# Anand1-PPG-Module.net
KiCad netlist of a schematic drawn in EAGLE
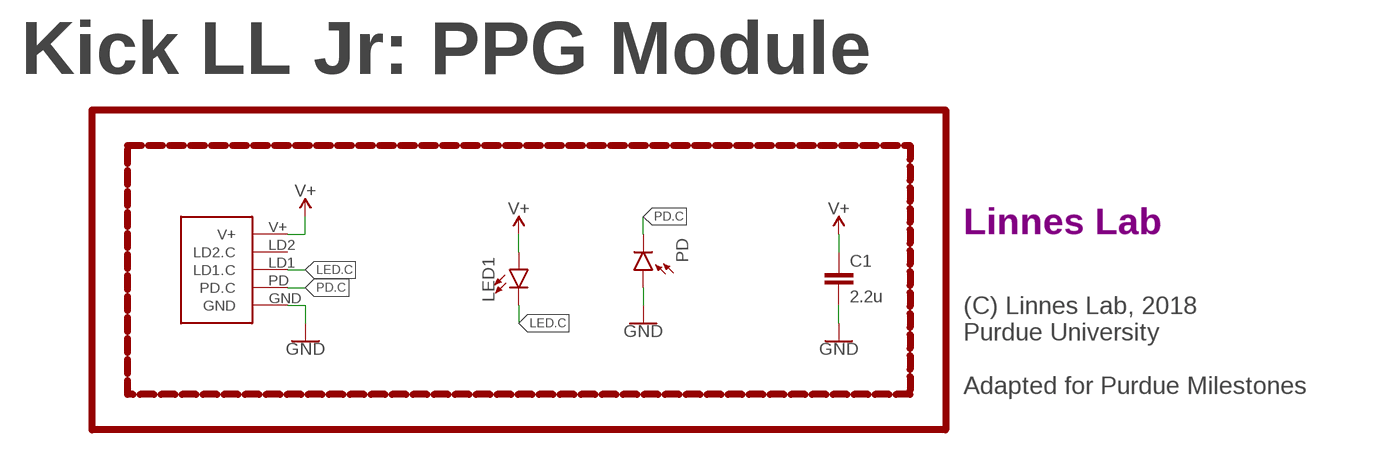
[diagram p0: schematic, sheet 1]

(export (version "E")
  (design (tool "Eeschema 10.0.6"))
  (components
    (comp (ref "C1")
      (value "2.2u")
      (footprint "eagle-import:C0603")
      (libsource (lib "eagle-import") (part "CAPACITOR0603"))
    )
    (comp (ref "J1")
      (value "PPG.MODULE.2")
      (footprint "eagle-import:PPG.MODULE.2")
      (libsource (lib "eagle-import") (part "PPG.MODULE.2"))
    )
    (comp (ref "LED1")
      (value "LED0805")
      (footprint "eagle-import:LED-0805")
      (libsource (lib "eagle-import") (part "LED0805"))
    )
    (comp (ref "PD")
      (value "PHOTODIODE.-SMD.GULLWING")
      (footprint "eagle-import:2-SMD.GULLWING")
      (libsource (lib "eagle-import") (part "PHOTODIODE.-SMD.GULLWING"))
    )
    (comp (ref "U$3")
      (value "LINNES.LAB.LOGO")
      (footprint "eagle-import:LINNES.LAB.LOGO")
      (libsource (lib "eagle-import") (part "LINNES.LAB.LOGO"))
    )
  )
  (nets
    (net (code "1") (name "GND") (class "Default")
      (node (ref "C1") (pin "2") (pinfunction "2_2") (pintype "passive"))
      (node (ref "J1") (pin "GND") (pinfunction "GND_GND") (pintype "bidirectional"))
      (node (ref "PD") (pin "+") (pinfunction "A_+") (pintype "passive"))
    )
    (net (code "2") (name "LED.C") (class "Default")
      (node (ref "J1") (pin "LD1") (pinfunction "LD1.C_LD1") (pintype "bidirectional"))
      (node (ref "LED1") (pin "C") (pinfunction "C_C") (pintype "passive"))
    )
    (net (code "3") (name "PD.C") (class "Default")
      (node (ref "J1") (pin "PD") (pinfunction "PD.C_PD") (pintype "bidirectional"))
      (node (ref "PD") (pin "-") (pinfunction "C_-") (pintype "passive"))
    )
    (net (code "4") (name "V+") (class "Default")
      (node (ref "C1") (pin "1") (pinfunction "1_1") (pintype "passive"))
      (node (ref "J1") (pin "V+") (pinfunction "V+_V+") (pintype "bidirectional"))
      (node (ref "LED1") (pin "A") (pinfunction "A_A") (pintype "passive"))
    )
    (net (code "5") (name "unconnected-(J1-LD2.C-PadLD2)") (class "Default")
      (node (ref "J1") (pin "LD2") (pinfunction "LD2.C_LD2") (pintype "bidirectional"))
    )
  )
)
